# CellCircuit.net
KiCad netlist of a schematic drawn in Altium Designer
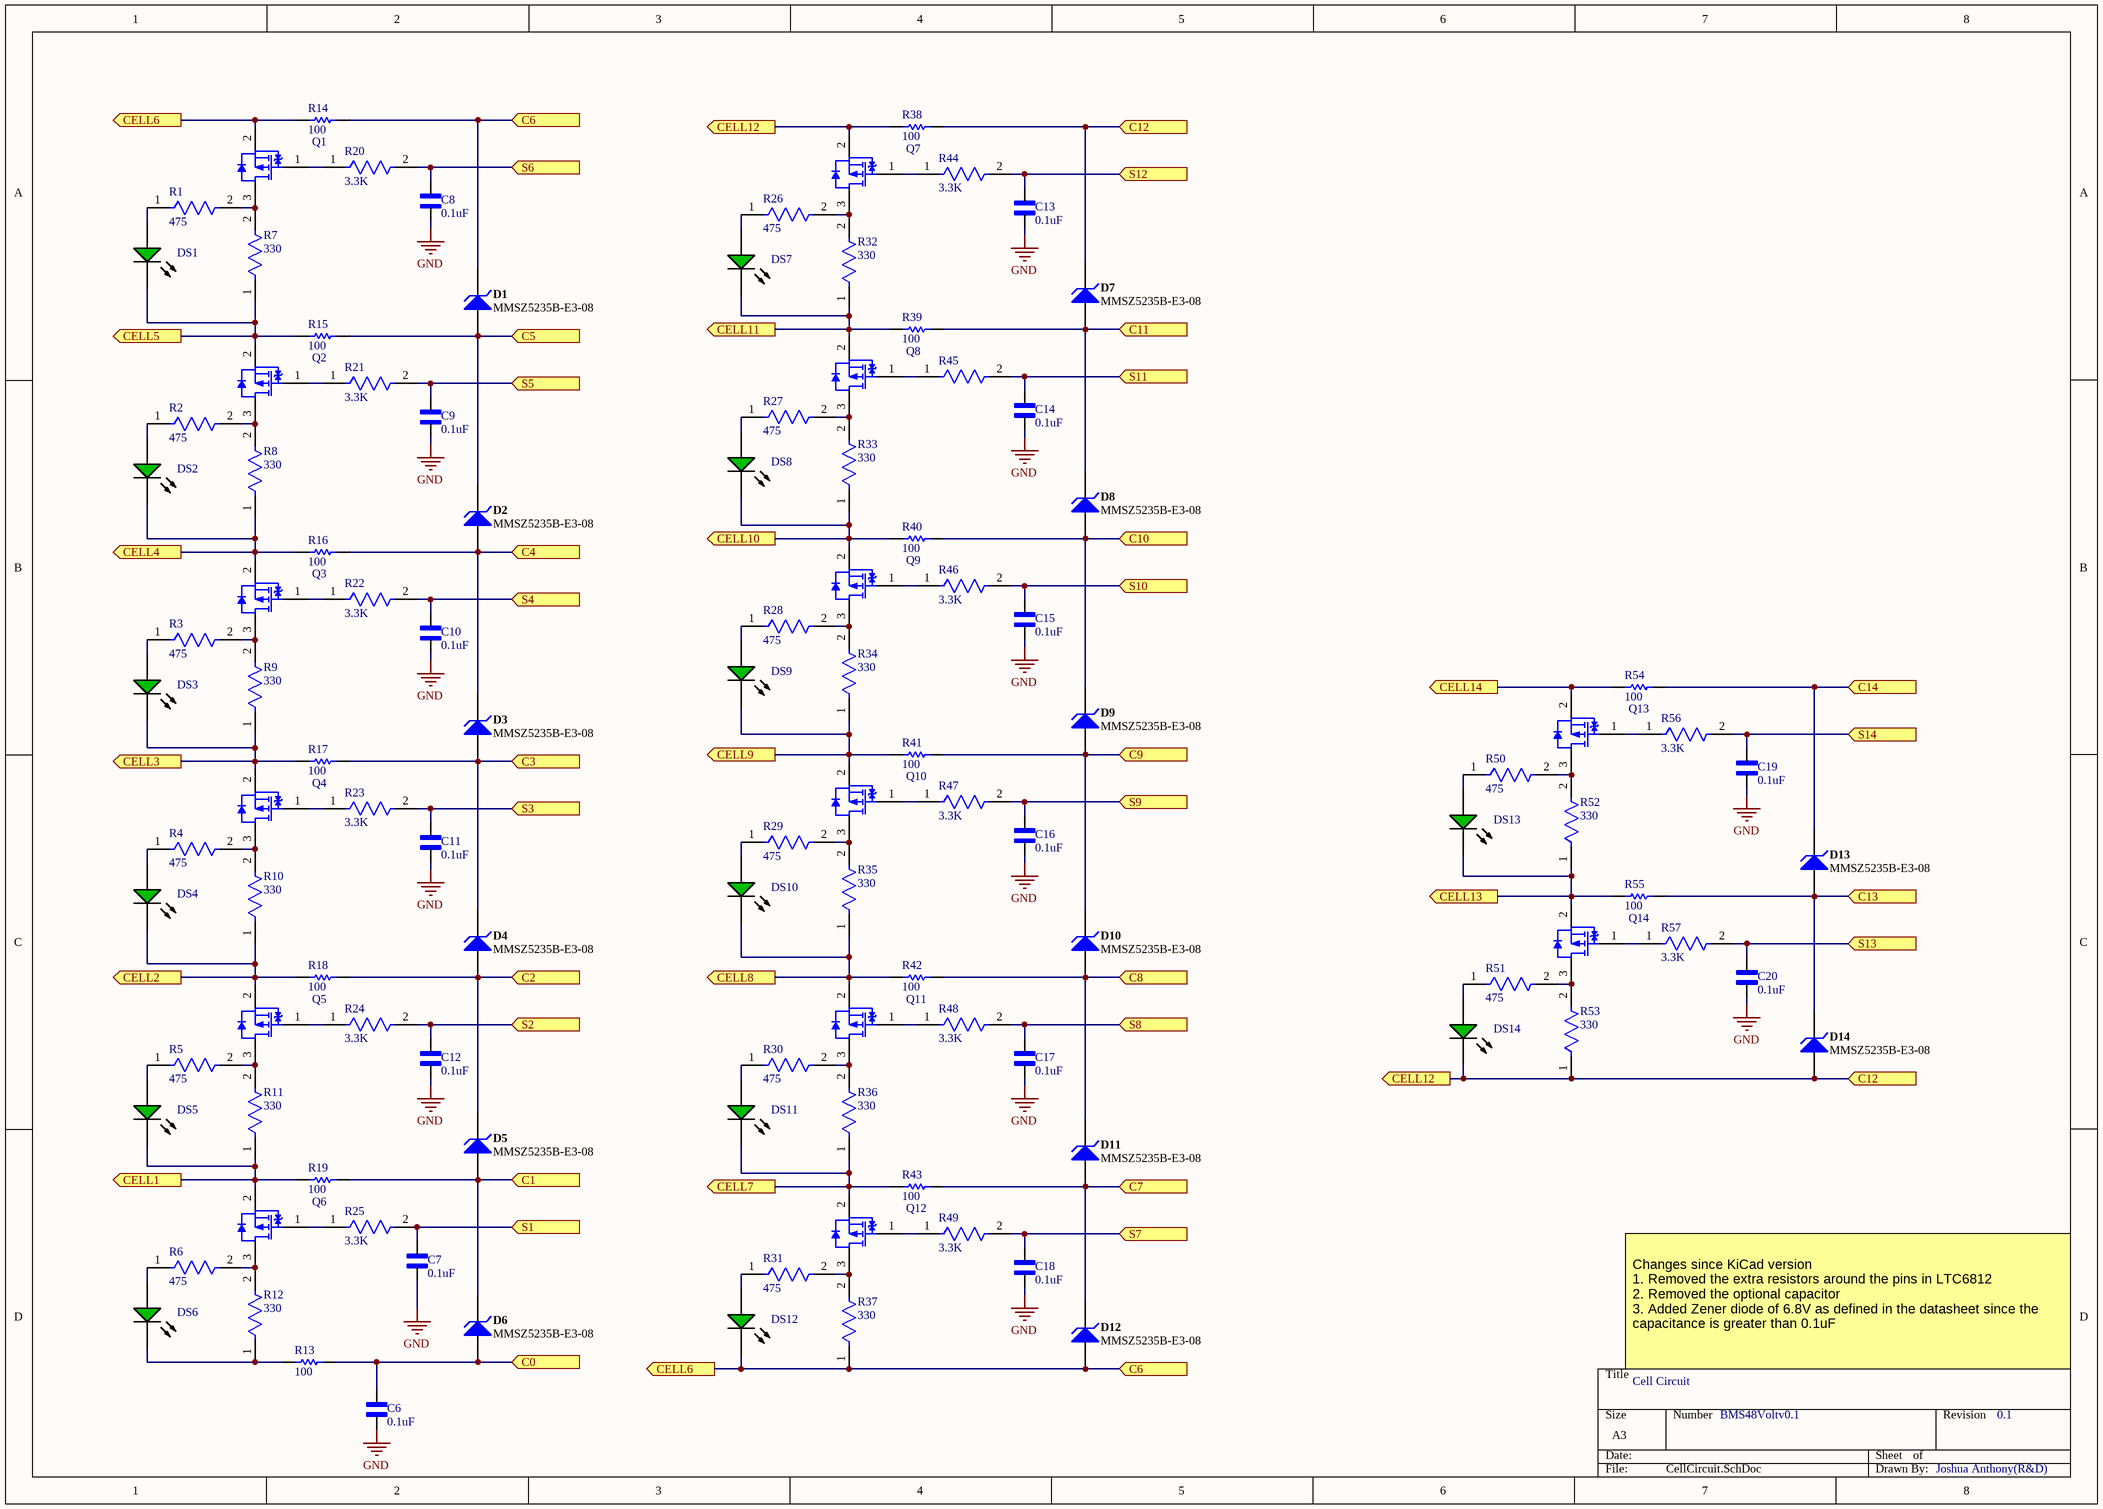
[diagram p0: CellCircuit.SchDoc]

(export (version "E")
  (design (tool "Eeschema 10.0.6"))
  (components
    (comp (ref "C6")
      (value "0.1uF")
      (footprint "CAPC1005X55N")
      (description "CAP CER 0.1UF 16V 10% X7R 0402")
      (fields (field (name "MF") "{'manufacturer': u'Murata'}") (field (name "MP") "GRM155R71C104KA88D"))
      (libsource (lib "SnapEDA_Library") (part "GRM155R71C104KA88D"))
    )
    (comp (ref "C7")
      (value "0.1uF")
      (footprint "CAPC1005X55N")
      (description "CAP CER 0.1UF 16V 10% X7R 0402")
      (fields (field (name "MF") "{'manufacturer': u'Murata'}") (field (name "MP") "GRM155R71C104KA88D"))
      (libsource (lib "SnapEDA_Library") (part "GRM155R71C104KA88D"))
    )
    (comp (ref "C8")
      (value "0.1uF")
      (footprint "CAPC1005X55N")
      (description "CAP CER 0.1UF 16V 10% X7R 0402")
      (fields (field (name "MF") "{'manufacturer': u'Murata'}") (field (name "MP") "GRM155R71C104KA88D"))
      (libsource (lib "SnapEDA_Library") (part "GRM155R71C104KA88D"))
    )
    (comp (ref "C9")
      (value "0.1uF")
      (footprint "CAPC1005X55N")
      (description "CAP CER 0.1UF 16V 10% X7R 0402")
      (fields (field (name "MF") "{'manufacturer': u'Murata'}") (field (name "MP") "GRM155R71C104KA88D"))
      (libsource (lib "SnapEDA_Library") (part "GRM155R71C104KA88D"))
    )
    (comp (ref "C10")
      (value "0.1uF")
      (footprint "CAPC1005X55N")
      (description "CAP CER 0.1UF 16V 10% X7R 0402")
      (fields (field (name "MF") "{'manufacturer': u'Murata'}") (field (name "MP") "GRM155R71C104KA88D"))
      (libsource (lib "SnapEDA_Library") (part "GRM155R71C104KA88D"))
    )
    (comp (ref "C11")
      (value "0.1uF")
      (footprint "CAPC1005X55N")
      (description "CAP CER 0.1UF 16V 10% X7R 0402")
      (fields (field (name "MF") "{'manufacturer': u'Murata'}") (field (name "MP") "GRM155R71C104KA88D"))
      (libsource (lib "SnapEDA_Library") (part "GRM155R71C104KA88D"))
    )
    (comp (ref "C12")
      (value "0.1uF")
      (footprint "CAPC1005X55N")
      (description "CAP CER 0.1UF 16V 10% X7R 0402")
      (fields (field (name "MF") "{'manufacturer': u'Murata'}") (field (name "MP") "GRM155R71C104KA88D"))
      (libsource (lib "SnapEDA_Library") (part "GRM155R71C104KA88D"))
    )
    (comp (ref "C13")
      (value "0.1uF")
      (footprint "CAPC1005X55N")
      (description "CAP CER 0.1UF 16V 10% X7R 0402")
      (fields (field (name "MF") "{'manufacturer': u'Murata'}") (field (name "MP") "GRM155R71C104KA88D"))
      (libsource (lib "SnapEDA_Library") (part "GRM155R71C104KA88D"))
    )
    (comp (ref "C14")
      (value "0.1uF")
      (footprint "CAPC1005X55N")
      (description "CAP CER 0.1UF 16V 10% X7R 0402")
      (fields (field (name "MF") "{'manufacturer': u'Murata'}") (field (name "MP") "GRM155R71C104KA88D"))
      (libsource (lib "SnapEDA_Library") (part "GRM155R71C104KA88D"))
    )
    (comp (ref "C15")
      (value "0.1uF")
      (footprint "CAPC1005X55N")
      (description "CAP CER 0.1UF 16V 10% X7R 0402")
      (fields (field (name "MF") "{'manufacturer': u'Murata'}") (field (name "MP") "GRM155R71C104KA88D"))
      (libsource (lib "SnapEDA_Library") (part "GRM155R71C104KA88D"))
    )
    (comp (ref "C16")
      (value "0.1uF")
      (footprint "CAPC1005X55N")
      (description "CAP CER 0.1UF 16V 10% X7R 0402")
      (fields (field (name "MF") "{'manufacturer': u'Murata'}") (field (name "MP") "GRM155R71C104KA88D"))
      (libsource (lib "SnapEDA_Library") (part "GRM155R71C104KA88D"))
    )
    (comp (ref "C17")
      (value "0.1uF")
      (footprint "CAPC1005X55N")
      (description "CAP CER 0.1UF 16V 10% X7R 0402")
      (fields (field (name "MF") "{'manufacturer': u'Murata'}") (field (name "MP") "GRM155R71C104KA88D"))
      (libsource (lib "SnapEDA_Library") (part "GRM155R71C104KA88D"))
    )
    (comp (ref "C18")
      (value "0.1uF")
      (footprint "CAPC1005X55N")
      (description "CAP CER 0.1UF 16V 10% X7R 0402")
      (fields (field (name "MF") "{'manufacturer': u'Murata'}") (field (name "MP") "GRM155R71C104KA88D"))
      (libsource (lib "SnapEDA_Library") (part "GRM155R71C104KA88D"))
    )
    (comp (ref "C19")
      (value "0.1uF")
      (footprint "CAPC1005X55N")
      (description "CAP CER 0.1UF 16V 10% X7R 0402")
      (fields (field (name "MF") "{'manufacturer': u'Murata'}") (field (name "MP") "GRM155R71C104KA88D"))
      (libsource (lib "SnapEDA_Library") (part "GRM155R71C104KA88D"))
    )
    (comp (ref "C20")
      (value "0.1uF")
      (footprint "CAPC1005X55N")
      (description "CAP CER 0.1UF 16V 10% X7R 0402")
      (fields (field (name "MF") "{'manufacturer': u'Murata'}") (field (name "MP") "GRM155R71C104KA88D"))
      (libsource (lib "SnapEDA_Library") (part "GRM155R71C104KA88D"))
    )
    (comp (ref "D1")
      (value "MMSZ5235B-E3-08")
      (footprint "VISH-SOD-123-2_V")
      (description "Small Signal Zener Diode, 6.8 V +/- 5%, -55 to 155 degC, 2-Pin SOD-123, RoHS, Tape and Reel")
      (fields (field (name "MANUFACTURER") "Vishay Semiconductor") (field (name "TOLERANCE") "+/- 5%"))
      (libsource (lib "Altium Content Vault") (part "VISH-DZEN_A1K2-2"))
    )
    (comp (ref "D2")
      (value "MMSZ5235B-E3-08")
      (footprint "VISH-SOD-123-2_V")
      (description "Small Signal Zener Diode, 6.8 V +/- 5%, -55 to 155 degC, 2-Pin SOD-123, RoHS, Tape and Reel")
      (fields (field (name "MANUFACTURER") "Vishay Semiconductor") (field (name "TOLERANCE") "+/- 5%"))
      (libsource (lib "Altium Content Vault") (part "VISH-DZEN_A1K2-2"))
    )
    (comp (ref "D3")
      (value "MMSZ5235B-E3-08")
      (footprint "VISH-SOD-123-2_V")
      (description "Small Signal Zener Diode, 6.8 V +/- 5%, -55 to 155 degC, 2-Pin SOD-123, RoHS, Tape and Reel")
      (fields (field (name "MANUFACTURER") "Vishay Semiconductor") (field (name "TOLERANCE") "+/- 5%"))
      (libsource (lib "Altium Content Vault") (part "VISH-DZEN_A1K2-2"))
    )
    (comp (ref "D4")
      (value "MMSZ5235B-E3-08")
      (footprint "VISH-SOD-123-2_V")
      (description "Small Signal Zener Diode, 6.8 V +/- 5%, -55 to 155 degC, 2-Pin SOD-123, RoHS, Tape and Reel")
      (fields (field (name "MANUFACTURER") "Vishay Semiconductor") (field (name "TOLERANCE") "+/- 5%"))
      (libsource (lib "Altium Content Vault") (part "VISH-DZEN_A1K2-2"))
    )
    (comp (ref "D5")
      (value "MMSZ5235B-E3-08")
      (footprint "VISH-SOD-123-2_V")
      (description "Small Signal Zener Diode, 6.8 V +/- 5%, -55 to 155 degC, 2-Pin SOD-123, RoHS, Tape and Reel")
      (fields (field (name "MANUFACTURER") "Vishay Semiconductor") (field (name "TOLERANCE") "+/- 5%"))
      (libsource (lib "Altium Content Vault") (part "VISH-DZEN_A1K2-2"))
    )
    (comp (ref "D6")
      (value "MMSZ5235B-E3-08")
      (footprint "VISH-SOD-123-2_V")
      (description "Small Signal Zener Diode, 6.8 V +/- 5%, -55 to 155 degC, 2-Pin SOD-123, RoHS, Tape and Reel")
      (fields (field (name "MANUFACTURER") "Vishay Semiconductor") (field (name "TOLERANCE") "+/- 5%"))
      (libsource (lib "Altium Content Vault") (part "VISH-DZEN_A1K2-2"))
    )
    (comp (ref "D7")
      (value "MMSZ5235B-E3-08")
      (footprint "VISH-SOD-123-2_V")
      (description "Small Signal Zener Diode, 6.8 V +/- 5%, -55 to 155 degC, 2-Pin SOD-123, RoHS, Tape and Reel")
      (fields (field (name "MANUFACTURER") "Vishay Semiconductor") (field (name "TOLERANCE") "+/- 5%"))
      (libsource (lib "Altium Content Vault") (part "VISH-DZEN_A1K2-2"))
    )
    (comp (ref "D8")
      (value "MMSZ5235B-E3-08")
      (footprint "VISH-SOD-123-2_V")
      (description "Small Signal Zener Diode, 6.8 V +/- 5%, -55 to 155 degC, 2-Pin SOD-123, RoHS, Tape and Reel")
      (fields (field (name "MANUFACTURER") "Vishay Semiconductor") (field (name "TOLERANCE") "+/- 5%"))
      (libsource (lib "Altium Content Vault") (part "VISH-DZEN_A1K2-2"))
    )
    (comp (ref "D9")
      (value "MMSZ5235B-E3-08")
      (footprint "VISH-SOD-123-2_V")
      (description "Small Signal Zener Diode, 6.8 V +/- 5%, -55 to 155 degC, 2-Pin SOD-123, RoHS, Tape and Reel")
      (fields (field (name "MANUFACTURER") "Vishay Semiconductor") (field (name "TOLERANCE") "+/- 5%"))
      (libsource (lib "Altium Content Vault") (part "VISH-DZEN_A1K2-2"))
    )
    (comp (ref "D10")
      (value "MMSZ5235B-E3-08")
      (footprint "VISH-SOD-123-2_V")
      (description "Small Signal Zener Diode, 6.8 V +/- 5%, -55 to 155 degC, 2-Pin SOD-123, RoHS, Tape and Reel")
      (fields (field (name "MANUFACTURER") "Vishay Semiconductor") (field (name "TOLERANCE") "+/- 5%"))
      (libsource (lib "Altium Content Vault") (part "VISH-DZEN_A1K2-2"))
    )
    (comp (ref "D11")
      (value "MMSZ5235B-E3-08")
      (footprint "VISH-SOD-123-2_V")
      (description "Small Signal Zener Diode, 6.8 V +/- 5%, -55 to 155 degC, 2-Pin SOD-123, RoHS, Tape and Reel")
      (fields (field (name "MANUFACTURER") "Vishay Semiconductor") (field (name "TOLERANCE") "+/- 5%"))
      (libsource (lib "Altium Content Vault") (part "VISH-DZEN_A1K2-2"))
    )
    (comp (ref "D12")
      (value "MMSZ5235B-E3-08")
      (footprint "VISH-SOD-123-2_V")
      (description "Small Signal Zener Diode, 6.8 V +/- 5%, -55 to 155 degC, 2-Pin SOD-123, RoHS, Tape and Reel")
      (fields (field (name "MANUFACTURER") "Vishay Semiconductor") (field (name "TOLERANCE") "+/- 5%"))
      (libsource (lib "Altium Content Vault") (part "VISH-DZEN_A1K2-2"))
    )
    (comp (ref "D13")
      (value "MMSZ5235B-E3-08")
      (footprint "VISH-SOD-123-2_V")
      (description "Small Signal Zener Diode, 6.8 V +/- 5%, -55 to 155 degC, 2-Pin SOD-123, RoHS, Tape and Reel")
      (fields (field (name "MANUFACTURER") "Vishay Semiconductor") (field (name "TOLERANCE") "+/- 5%"))
      (libsource (lib "Altium Content Vault") (part "VISH-DZEN_A1K2-2"))
    )
    (comp (ref "D14")
      (value "MMSZ5235B-E3-08")
      (footprint "VISH-SOD-123-2_V")
      (description "Small Signal Zener Diode, 6.8 V +/- 5%, -55 to 155 degC, 2-Pin SOD-123, RoHS, Tape and Reel")
      (fields (field (name "MANUFACTURER") "Vishay Semiconductor") (field (name "TOLERANCE") "+/- 5%"))
      (libsource (lib "Altium Content Vault") (part "VISH-DZEN_A1K2-2"))
    )
    (comp (ref "DS1")
      (value "HSMG-C170")
      (footprint "AVAG-HSMX-C170_V")
      (description "Chip LED, Green, 2.2 V, -40 to 85 degC, 2-Pin SMD, Pb-Free, Tape and Reel")
      (fields (field (name "MANUFACTURER") "Avago"))
      (libsource (lib "Altium Content Vault") (part "LED_GREEN_A1K2-2"))
    )
    (comp (ref "DS2")
      (value "HSMG-C170")
      (footprint "AVAG-HSMX-C170_V")
      (description "Chip LED, Green, 2.2 V, -40 to 85 degC, 2-Pin SMD, Pb-Free, Tape and Reel")
      (fields (field (name "MANUFACTURER") "Avago"))
      (libsource (lib "Altium Content Vault") (part "LED_GREEN_A1K2-2"))
    )
    (comp (ref "DS3")
      (value "HSMG-C170")
      (footprint "AVAG-HSMX-C170_V")
      (description "Chip LED, Green, 2.2 V, -40 to 85 degC, 2-Pin SMD, Pb-Free, Tape and Reel")
      (fields (field (name "MANUFACTURER") "Avago"))
      (libsource (lib "Altium Content Vault") (part "LED_GREEN_A1K2-2"))
    )
    (comp (ref "DS4")
      (value "HSMG-C170")
      (footprint "AVAG-HSMX-C170_V")
      (description "Chip LED, Green, 2.2 V, -40 to 85 degC, 2-Pin SMD, Pb-Free, Tape and Reel")
      (fields (field (name "MANUFACTURER") "Avago"))
      (libsource (lib "Altium Content Vault") (part "LED_GREEN_A1K2-2"))
    )
    (comp (ref "DS5")
      (value "HSMG-C170")
      (footprint "AVAG-HSMX-C170_V")
      (description "Chip LED, Green, 2.2 V, -40 to 85 degC, 2-Pin SMD, Pb-Free, Tape and Reel")
      (fields (field (name "MANUFACTURER") "Avago"))
      (libsource (lib "Altium Content Vault") (part "LED_GREEN_A1K2-2"))
    )
    (comp (ref "DS6")
      (value "HSMG-C170")
      (footprint "AVAG-HSMX-C170_V")
      (description "Chip LED, Green, 2.2 V, -40 to 85 degC, 2-Pin SMD, Pb-Free, Tape and Reel")
      (fields (field (name "MANUFACTURER") "Avago"))
      (libsource (lib "Altium Content Vault") (part "LED_GREEN_A1K2-2"))
    )
    (comp (ref "DS7")
      (value "HSMG-C170")
      (footprint "AVAG-HSMX-C170_V")
      (description "Chip LED, Green, 2.2 V, -40 to 85 degC, 2-Pin SMD, Pb-Free, Tape and Reel")
      (fields (field (name "MANUFACTURER") "Avago"))
      (libsource (lib "Altium Content Vault") (part "LED_GREEN_A1K2-2"))
    )
    (comp (ref "DS8")
      (value "HSMG-C170")
      (footprint "AVAG-HSMX-C170_V")
      (description "Chip LED, Green, 2.2 V, -40 to 85 degC, 2-Pin SMD, Pb-Free, Tape and Reel")
      (fields (field (name "MANUFACTURER") "Avago"))
      (libsource (lib "Altium Content Vault") (part "LED_GREEN_A1K2-2"))
    )
    (comp (ref "DS9")
      (value "HSMG-C170")
      (footprint "AVAG-HSMX-C170_V")
      (description "Chip LED, Green, 2.2 V, -40 to 85 degC, 2-Pin SMD, Pb-Free, Tape and Reel")
      (fields (field (name "MANUFACTURER") "Avago"))
      (libsource (lib "Altium Content Vault") (part "LED_GREEN_A1K2-2"))
    )
    (comp (ref "DS10")
      (value "HSMG-C170")
      (footprint "AVAG-HSMX-C170_V")
      (description "Chip LED, Green, 2.2 V, -40 to 85 degC, 2-Pin SMD, Pb-Free, Tape and Reel")
      (fields (field (name "MANUFACTURER") "Avago"))
      (libsource (lib "Altium Content Vault") (part "LED_GREEN_A1K2-2"))
    )
    (comp (ref "DS11")
      (value "HSMG-C170")
      (footprint "AVAG-HSMX-C170_V")
      (description "Chip LED, Green, 2.2 V, -40 to 85 degC, 2-Pin SMD, Pb-Free, Tape and Reel")
      (fields (field (name "MANUFACTURER") "Avago"))
      (libsource (lib "Altium Content Vault") (part "LED_GREEN_A1K2-2"))
    )
    (comp (ref "DS12")
      (value "HSMG-C170")
      (footprint "AVAG-HSMX-C170_V")
      (description "Chip LED, Green, 2.2 V, -40 to 85 degC, 2-Pin SMD, Pb-Free, Tape and Reel")
      (fields (field (name "MANUFACTURER") "Avago"))
      (libsource (lib "Altium Content Vault") (part "LED_GREEN_A1K2-2"))
    )
    (comp (ref "DS13")
      (value "HSMG-C170")
      (footprint "AVAG-HSMX-C170_V")
      (description "Chip LED, Green, 2.2 V, -40 to 85 degC, 2-Pin SMD, Pb-Free, Tape and Reel")
      (fields (field (name "MANUFACTURER") "Avago"))
      (libsource (lib "Altium Content Vault") (part "LED_GREEN_A1K2-2"))
    )
    (comp (ref "DS14")
      (value "HSMG-C170")
      (footprint "AVAG-HSMX-C170_V")
      (description "Chip LED, Green, 2.2 V, -40 to 85 degC, 2-Pin SMD, Pb-Free, Tape and Reel")
      (fields (field (name "MANUFACTURER") "Avago"))
      (libsource (lib "Altium Content Vault") (part "LED_GREEN_A1K2-2"))
    )
    (comp (ref "Q1")
      (value "BSS308PE")
      (footprint "INF-PG-SOT23_L")
      (fields (field (name "MANUFACTURER") "Infineon"))
      (libsource (lib "Altium Content Vault") (part "INF-BSS3XXPE-PG-SOT23-3"))
    )
    (comp (ref "Q2")
      (value "BSS308PE")
      (footprint "INF-PG-SOT23_L")
      (fields (field (name "MANUFACTURER") "Infineon"))
      (libsource (lib "Altium Content Vault") (part "INF-BSS3XXPE-PG-SOT23-3"))
    )
    (comp (ref "Q3")
      (value "BSS308PE")
      (footprint "INF-PG-SOT23_L")
      (fields (field (name "MANUFACTURER") "Infineon"))
      (libsource (lib "Altium Content Vault") (part "INF-BSS3XXPE-PG-SOT23-3"))
    )
    (comp (ref "Q4")
      (value "BSS308PE")
      (footprint "INF-PG-SOT23_L")
      (fields (field (name "MANUFACTURER") "Infineon"))
      (libsource (lib "Altium Content Vault") (part "INF-BSS3XXPE-PG-SOT23-3"))
    )
    (comp (ref "Q5")
      (value "BSS308PE")
      (footprint "INF-PG-SOT23_L")
      (fields (field (name "MANUFACTURER") "Infineon"))
      (libsource (lib "Altium Content Vault") (part "INF-BSS3XXPE-PG-SOT23-3"))
    )
    (comp (ref "Q6")
      (value "BSS308PE")
      (footprint "INF-PG-SOT23_L")
      (fields (field (name "MANUFACTURER") "Infineon"))
      (libsource (lib "Altium Content Vault") (part "INF-BSS3XXPE-PG-SOT23-3"))
    )
    (comp (ref "Q7")
      (value "BSS308PE")
      (footprint "INF-PG-SOT23_L")
      (fields (field (name "MANUFACTURER") "Infineon"))
      (libsource (lib "Altium Content Vault") (part "INF-BSS3XXPE-PG-SOT23-3"))
    )
    (comp (ref "Q8")
      (value "BSS308PE")
      (footprint "INF-PG-SOT23_L")
      (fields (field (name "MANUFACTURER") "Infineon"))
      (libsource (lib "Altium Content Vault") (part "INF-BSS3XXPE-PG-SOT23-3"))
    )
    (comp (ref "Q9")
      (value "BSS308PE")
      (footprint "INF-PG-SOT23_L")
      (fields (field (name "MANUFACTURER") "Infineon"))
      (libsource (lib "Altium Content Vault") (part "INF-BSS3XXPE-PG-SOT23-3"))
    )
    (comp (ref "Q10")
      (value "BSS308PE")
      (footprint "INF-PG-SOT23_L")
      (fields (field (name "MANUFACTURER") "Infineon"))
      (libsource (lib "Altium Content Vault") (part "INF-BSS3XXPE-PG-SOT23-3"))
    )
    (comp (ref "Q11")
      (value "BSS308PE")
      (footprint "INF-PG-SOT23_L")
      (fields (field (name "MANUFACTURER") "Infineon"))
      (libsource (lib "Altium Content Vault") (part "INF-BSS3XXPE-PG-SOT23-3"))
    )
    (comp (ref "Q12")
      (value "BSS308PE")
      (footprint "INF-PG-SOT23_L")
      (fields (field (name "MANUFACTURER") "Infineon"))
      (libsource (lib "Altium Content Vault") (part "INF-BSS3XXPE-PG-SOT23-3"))
    )
    (comp (ref "Q13")
      (value "BSS308PE")
      (footprint "INF-PG-SOT23_L")
      (fields (field (name "MANUFACTURER") "Infineon"))
      (libsource (lib "Altium Content Vault") (part "INF-BSS3XXPE-PG-SOT23-3"))
    )
    (comp (ref "Q14")
      (value "BSS308PE")
      (footprint "INF-PG-SOT23_L")
      (fields (field (name "MANUFACTURER") "Infineon"))
      (libsource (lib "Altium Content Vault") (part "INF-BSS3XXPE-PG-SOT23-3"))
    )
    (comp (ref "R1")
      (value "475")
      (footprint "FP-CRCW0402-e3-IPC_C")
      (description "RES Thick Film, 475Ω, 1%, 0.063W, 100ppm/°C, 0402")
      (fields (field (name "TOLERANCE") "1%"))
      (libsource (lib "Altium Content Vault") (part "1029c3af85768c4190bb7ad29bc67b5"))
    )
    (comp (ref "R2")
      (value "475")
      (footprint "FP-CRCW0402-e3-IPC_C")
      (description "RES Thick Film, 475Ω, 1%, 0.063W, 100ppm/°C, 0402")
      (fields (field (name "TOLERANCE") "1%"))
      (libsource (lib "Altium Content Vault") (part "1029c3af85768c4190bb7ad29bc67b5"))
    )
    (comp (ref "R3")
      (value "475")
      (footprint "FP-CRCW0402-e3-IPC_C")
      (description "RES Thick Film, 475Ω, 1%, 0.063W, 100ppm/°C, 0402")
      (fields (field (name "TOLERANCE") "1%"))
      (libsource (lib "Altium Content Vault") (part "1029c3af85768c4190bb7ad29bc67b5"))
    )
    (comp (ref "R4")
      (value "475")
      (footprint "FP-CRCW0402-e3-IPC_C")
      (description "RES Thick Film, 475Ω, 1%, 0.063W, 100ppm/°C, 0402")
      (fields (field (name "TOLERANCE") "1%"))
      (libsource (lib "Altium Content Vault") (part "1029c3af85768c4190bb7ad29bc67b5"))
    )
    (comp (ref "R5")
      (value "475")
      (footprint "FP-CRCW0402-e3-IPC_C")
      (description "RES Thick Film, 475Ω, 1%, 0.063W, 100ppm/°C, 0402")
      (fields (field (name "TOLERANCE") "1%"))
      (libsource (lib "Altium Content Vault") (part "1029c3af85768c4190bb7ad29bc67b5"))
    )
    (comp (ref "R6")
      (value "475")
      (footprint "FP-CRCW0402-e3-IPC_C")
      (description "RES Thick Film, 475Ω, 1%, 0.063W, 100ppm/°C, 0402")
      (fields (field (name "TOLERANCE") "1%"))
      (libsource (lib "Altium Content Vault") (part "1029c3af85768c4190bb7ad29bc67b5"))
    )
    (comp (ref "R7")
      (value "330")
      (footprint "FP-CRCW0603-e3-MFG")
      (description "RES Thick Film, 330Ω, 1%, 0.1W, 100ppm/°C, 0603")
      (fields (field (name "TOLERANCE") "1%"))
      (libsource (lib "Altium Content Vault") (part "1029c3af85768c4190bb7ad29bc67b5"))
    )
    (comp (ref "R8")
      (value "330")
      (footprint "FP-CRCW0603-e3-MFG")
      (description "RES Thick Film, 330Ω, 1%, 0.1W, 100ppm/°C, 0603")
      (fields (field (name "TOLERANCE") "1%"))
      (libsource (lib "Altium Content Vault") (part "1029c3af85768c4190bb7ad29bc67b5"))
    )
    (comp (ref "R9")
      (value "330")
      (footprint "FP-CRCW0603-e3-MFG")
      (description "RES Thick Film, 330Ω, 1%, 0.1W, 100ppm/°C, 0603")
      (fields (field (name "TOLERANCE") "1%"))
      (libsource (lib "Altium Content Vault") (part "1029c3af85768c4190bb7ad29bc67b5"))
    )
    (comp (ref "R10")
      (value "330")
      (footprint "FP-CRCW0603-e3-MFG")
      (description "RES Thick Film, 330Ω, 1%, 0.1W, 100ppm/°C, 0603")
      (fields (field (name "TOLERANCE") "1%"))
      (libsource (lib "Altium Content Vault") (part "1029c3af85768c4190bb7ad29bc67b5"))
    )
    (comp (ref "R11")
      (value "330")
      (footprint "FP-CRCW0603-e3-MFG")
      (description "RES Thick Film, 330Ω, 1%, 0.1W, 100ppm/°C, 0603")
      (fields (field (name "TOLERANCE") "1%"))
      (libsource (lib "Altium Content Vault") (part "1029c3af85768c4190bb7ad29bc67b5"))
    )
    (comp (ref "R12")
      (value "330")
      (footprint "FP-CRCW0603-e3-MFG")
      (description "RES Thick Film, 330Ω, 1%, 0.1W, 100ppm/°C, 0603")
      (fields (field (name "TOLERANCE") "1%"))
      (libsource (lib "Altium Content Vault") (part "1029c3af85768c4190bb7ad29bc67b5"))
    )
    (comp (ref "R13")
      (value "100")
      (footprint "RESC1005X40X25LL05T05")
      (description "Chip Resistor, 100 Ohm, +/- 1%, 100 mW, -55 to 155 degC, 0402 (1005 Metric), RoHS, Tape and Reel")
      (fields (field (name "MANUFACTURER") "Basic Passives") (field (name "TOLERANCE") "1%"))
      (libsource (lib "Altium Content Vault") (part "RES-2"))
    )
    (comp (ref "R14")
      (value "100")
      (footprint "RESC1005X40X25LL05T05")
      (description "Chip Resistor, 100 Ohm, +/- 1%, 100 mW, -55 to 155 degC, 0402 (1005 Metric), RoHS, Tape and Reel")
      (fields (field (name "MANUFACTURER") "Basic Passives") (field (name "TOLERANCE") "1%"))
      (libsource (lib "Altium Content Vault") (part "RES-2"))
    )
    (comp (ref "R15")
      (value "100")
      (footprint "RESC1005X40X25LL05T05")
      (description "Chip Resistor, 100 Ohm, +/- 1%, 100 mW, -55 to 155 degC, 0402 (1005 Metric), RoHS, Tape and Reel")
      (fields (field (name "MANUFACTURER") "Basic Passives") (field (name "TOLERANCE") "1%"))
      (libsource (lib "Altium Content Vault") (part "RES-2"))
    )
    (comp (ref "R16")
      (value "100")
      (footprint "RESC1005X40X25LL05T05")
      (description "Chip Resistor, 100 Ohm, +/- 1%, 100 mW, -55 to 155 degC, 0402 (1005 Metric), RoHS, Tape and Reel")
      (fields (field (name "MANUFACTURER") "Basic Passives") (field (name "TOLERANCE") "1%"))
      (libsource (lib "Altium Content Vault") (part "RES-2"))
    )
    (comp (ref "R17")
      (value "100")
      (footprint "RESC1005X40X25LL05T05")
      (description "Chip Resistor, 100 Ohm, +/- 1%, 100 mW, -55 to 155 degC, 0402 (1005 Metric), RoHS, Tape and Reel")
      (fields (field (name "MANUFACTURER") "Basic Passives") (field (name "TOLERANCE") "1%"))
      (libsource (lib "Altium Content Vault") (part "RES-2"))
    )
    (comp (ref "R18")
      (value "100")
      (footprint "RESC1005X40X25LL05T05")
      (description "Chip Resistor, 100 Ohm, +/- 1%, 100 mW, -55 to 155 degC, 0402 (1005 Metric), RoHS, Tape and Reel")
      (fields (field (name "MANUFACTURER") "Basic Passives") (field (name "TOLERANCE") "1%"))
      (libsource (lib "Altium Content Vault") (part "RES-2"))
    )
    (comp (ref "R19")
      (value "100")
      (footprint "RESC1005X40X25LL05T05")
      (description "Chip Resistor, 100 Ohm, +/- 1%, 100 mW, -55 to 155 degC, 0402 (1005 Metric), RoHS, Tape and Reel")
      (fields (field (name "MANUFACTURER") "Basic Passives") (field (name "TOLERANCE") "1%"))
      (libsource (lib "Altium Content Vault") (part "RES-2"))
    )
    (comp (ref "R20")
      (value "3.3K")
      (footprint "FP-RMCF2512-IPC_C")
      (description "3.3kΩ ±5% 1W 2512 Thick Film Chip Resistor AEC-Q200 compliant")
      (fields (field (name "TOLERANCE") "5%"))
      (libsource (lib "Altium Content Vault") (part "1029c3af85768c4190bb7ad29bc67b5"))
    )
    (comp (ref "R21")
      (value "3.3K")
      (footprint "FP-RMCF2512-IPC_C")
      (description "3.3kΩ ±5% 1W 2512 Thick Film Chip Resistor AEC-Q200 compliant")
      (fields (field (name "TOLERANCE") "5%"))
      (libsource (lib "Altium Content Vault") (part "1029c3af85768c4190bb7ad29bc67b5"))
    )
    (comp (ref "R22")
      (value "3.3K")
      (footprint "FP-RMCF2512-IPC_C")
      (description "3.3kΩ ±5% 1W 2512 Thick Film Chip Resistor AEC-Q200 compliant")
      (fields (field (name "TOLERANCE") "5%"))
      (libsource (lib "Altium Content Vault") (part "1029c3af85768c4190bb7ad29bc67b5"))
    )
    (comp (ref "R23")
      (value "3.3K")
      (footprint "FP-RMCF2512-IPC_C")
      (description "3.3kΩ ±5% 1W 2512 Thick Film Chip Resistor AEC-Q200 compliant")
      (fields (field (name "TOLERANCE") "5%"))
      (libsource (lib "Altium Content Vault") (part "1029c3af85768c4190bb7ad29bc67b5"))
    )
    (comp (ref "R24")
      (value "3.3K")
      (footprint "FP-RMCF2512-IPC_C")
      (description "3.3kΩ ±5% 1W 2512 Thick Film Chip Resistor AEC-Q200 compliant")
      (fields (field (name "TOLERANCE") "5%"))
      (libsource (lib "Altium Content Vault") (part "1029c3af85768c4190bb7ad29bc67b5"))
    )
    (comp (ref "R25")
      (value "3.3K")
      (footprint "FP-RMCF2512-IPC_C")
      (description "3.3kΩ ±5% 1W 2512 Thick Film Chip Resistor AEC-Q200 compliant")
      (fields (field (name "TOLERANCE") "5%"))
      (libsource (lib "Altium Content Vault") (part "1029c3af85768c4190bb7ad29bc67b5"))
    )
    (comp (ref "R26")
      (value "475")
      (footprint "FP-CRCW0402-e3-IPC_C")
      (description "RES Thick Film, 475Ω, 1%, 0.063W, 100ppm/°C, 0402")
      (fields (field (name "TOLERANCE") "1%"))
      (libsource (lib "Altium Content Vault") (part "1029c3af85768c4190bb7ad29bc67b5"))
    )
    (comp (ref "R27")
      (value "475")
      (footprint "FP-CRCW0402-e3-IPC_C")
      (description "RES Thick Film, 475Ω, 1%, 0.063W, 100ppm/°C, 0402")
      (fields (field (name "TOLERANCE") "1%"))
      (libsource (lib "Altium Content Vault") (part "1029c3af85768c4190bb7ad29bc67b5"))
    )
    (comp (ref "R28")
      (value "475")
      (footprint "FP-CRCW0402-e3-IPC_C")
      (description "RES Thick Film, 475Ω, 1%, 0.063W, 100ppm/°C, 0402")
      (fields (field (name "TOLERANCE") "1%"))
      (libsource (lib "Altium Content Vault") (part "1029c3af85768c4190bb7ad29bc67b5"))
    )
    (comp (ref "R29")
      (value "475")
      (footprint "FP-CRCW0402-e3-IPC_C")
      (description "RES Thick Film, 475Ω, 1%, 0.063W, 100ppm/°C, 0402")
      (fields (field (name "TOLERANCE") "1%"))
      (libsource (lib "Altium Content Vault") (part "1029c3af85768c4190bb7ad29bc67b5"))
    )
    (comp (ref "R30")
      (value "475")
      (footprint "FP-CRCW0402-e3-IPC_C")
      (description "RES Thick Film, 475Ω, 1%, 0.063W, 100ppm/°C, 0402")
      (fields (field (name "TOLERANCE") "1%"))
      (libsource (lib "Altium Content Vault") (part "1029c3af85768c4190bb7ad29bc67b5"))
    )
    (comp (ref "R31")
      (value "475")
      (footprint "FP-CRCW0402-e3-IPC_C")
      (description "RES Thick Film, 475Ω, 1%, 0.063W, 100ppm/°C, 0402")
      (fields (field (name "TOLERANCE") "1%"))
      (libsource (lib "Altium Content Vault") (part "1029c3af85768c4190bb7ad29bc67b5"))
    )
    (comp (ref "R32")
      (value "330")
      (footprint "FP-CRCW0603-e3-MFG")
      (description "RES Thick Film, 330Ω, 1%, 0.1W, 100ppm/°C, 0603")
      (fields (field (name "TOLERANCE") "1%"))
      (libsource (lib "Altium Content Vault") (part "1029c3af85768c4190bb7ad29bc67b5"))
    )
    (comp (ref "R33")
      (value "330")
      (footprint "FP-CRCW0603-e3-MFG")
      (description "RES Thick Film, 330Ω, 1%, 0.1W, 100ppm/°C, 0603")
      (fields (field (name "TOLERANCE") "1%"))
      (libsource (lib "Altium Content Vault") (part "1029c3af85768c4190bb7ad29bc67b5"))
    )
    (comp (ref "R34")
      (value "330")
      (footprint "FP-CRCW0603-e3-MFG")
      (description "RES Thick Film, 330Ω, 1%, 0.1W, 100ppm/°C, 0603")
      (fields (field (name "TOLERANCE") "1%"))
      (libsource (lib "Altium Content Vault") (part "1029c3af85768c4190bb7ad29bc67b5"))
    )
    (comp (ref "R35")
      (value "330")
      (footprint "FP-CRCW0603-e3-MFG")
      (description "RES Thick Film, 330Ω, 1%, 0.1W, 100ppm/°C, 0603")
      (fields (field (name "TOLERANCE") "1%"))
      (libsource (lib "Altium Content Vault") (part "1029c3af85768c4190bb7ad29bc67b5"))
    )
    (comp (ref "R36")
      (value "330")
      (footprint "FP-CRCW0603-e3-MFG")
      (description "RES Thick Film, 330Ω, 1%, 0.1W, 100ppm/°C, 0603")
      (fields (field (name "TOLERANCE") "1%"))
      (libsource (lib "Altium Content Vault") (part "1029c3af85768c4190bb7ad29bc67b5"))
    )
    (comp (ref "R37")
      (value "330")
      (footprint "FP-CRCW0603-e3-MFG")
      (description "RES Thick Film, 330Ω, 1%, 0.1W, 100ppm/°C, 0603")
      (fields (field (name "TOLERANCE") "1%"))
      (libsource (lib "Altium Content Vault") (part "1029c3af85768c4190bb7ad29bc67b5"))
    )
    (comp (ref "R38")
      (value "100")
      (footprint "RESC1005X40X25LL05T05")
      (description "Chip Resistor, 100 Ohm, +/- 1%, 100 mW, -55 to 155 degC, 0402 (1005 Metric), RoHS, Tape and Reel")
      (fields (field (name "MANUFACTURER") "Basic Passives") (field (name "TOLERANCE") "1%"))
      (libsource (lib "Altium Content Vault") (part "RES-2"))
    )
    (comp (ref "R39")
      (value "100")
      (footprint "RESC1005X40X25LL05T05")
      (description "Chip Resistor, 100 Ohm, +/- 1%, 100 mW, -55 to 155 degC, 0402 (1005 Metric), RoHS, Tape and Reel")
      (fields (field (name "MANUFACTURER") "Basic Passives") (field (name "TOLERANCE") "1%"))
      (libsource (lib "Altium Content Vault") (part "RES-2"))
    )
    (comp (ref "R40")
      (value "100")
      (footprint "RESC1005X40X25LL05T05")
      (description "Chip Resistor, 100 Ohm, +/- 1%, 100 mW, -55 to 155 degC, 0402 (1005 Metric), RoHS, Tape and Reel")
      (fields (field (name "MANUFACTURER") "Basic Passives") (field (name "TOLERANCE") "1%"))
      (libsource (lib "Altium Content Vault") (part "RES-2"))
    )
    (comp (ref "R41")
      (value "100")
      (footprint "RESC1005X40X25LL05T05")
      (description "Chip Resistor, 100 Ohm, +/- 1%, 100 mW, -55 to 155 degC, 0402 (1005 Metric), RoHS, Tape and Reel")
      (fields (field (name "MANUFACTURER") "Basic Passives") (field (name "TOLERANCE") "1%"))
      (libsource (lib "Altium Content Vault") (part "RES-2"))
    )
    (comp (ref "R42")
      (value "100")
      (footprint "RESC1005X40X25LL05T05")
      (description "Chip Resistor, 100 Ohm, +/- 1%, 100 mW, -55 to 155 degC, 0402 (1005 Metric), RoHS, Tape and Reel")
      (fields (field (name "MANUFACTURER") "Basic Passives") (field (name "TOLERANCE") "1%"))
      (libsource (lib "Altium Content Vault") (part "RES-2"))
    )
    (comp (ref "R43")
      (value "100")
      (footprint "RESC1005X40X25LL05T05")
      (description "Chip Resistor, 100 Ohm, +/- 1%, 100 mW, -55 to 155 degC, 0402 (1005 Metric), RoHS, Tape and Reel")
      (fields (field (name "MANUFACTURER") "Basic Passives") (field (name "TOLERANCE") "1%"))
      (libsource (lib "Altium Content Vault") (part "RES-2"))
    )
    (comp (ref "R44")
      (value "3.3K")
      (footprint "FP-RMCF2512-IPC_C")
      (description "3.3kΩ ±5% 1W 2512 Thick Film Chip Resistor AEC-Q200 compliant")
      (fields (field (name "TOLERANCE") "5%"))
      (libsource (lib "Altium Content Vault") (part "1029c3af85768c4190bb7ad29bc67b5"))
    )
    (comp (ref "R45")
      (value "RMCF2512JT3K30")
      (footprint "FP-RMCF2512-IPC_C")
      (description "3.3kΩ ±5% 1W 2512 Thick Film Chip Resistor AEC-Q200 compliant")
      (fields (field (name "TOLERANCE") "5%"))
      (libsource (lib "Altium Content Vault") (part "1029c3af85768c4190bb7ad29bc67b5"))
    )
    (comp (ref "R46")
      (value "3.3K")
      (footprint "FP-RMCF2512-IPC_C")
      (description "3.3kΩ ±5% 1W 2512 Thick Film Chip Resistor AEC-Q200 compliant")
      (fields (field (name "TOLERANCE") "5%"))
      (libsource (lib "Altium Content Vault") (part "1029c3af85768c4190bb7ad29bc67b5"))
    )
    (comp (ref "R47")
      (value "3.3K")
      (footprint "FP-RMCF2512-IPC_C")
      (description "3.3kΩ ±5% 1W 2512 Thick Film Chip Resistor AEC-Q200 compliant")
      (fields (field (name "TOLERANCE") "5%"))
      (libsource (lib "Altium Content Vault") (part "1029c3af85768c4190bb7ad29bc67b5"))
    )
    (comp (ref "R48")
      (value "3.3K")
      (footprint "FP-RMCF2512-IPC_C")
      (description "3.3kΩ ±5% 1W 2512 Thick Film Chip Resistor AEC-Q200 compliant")
      (fields (field (name "TOLERANCE") "5%"))
      (libsource (lib "Altium Content Vault") (part "1029c3af85768c4190bb7ad29bc67b5"))
    )
    (comp (ref "R49")
      (value "3.3K")
      (footprint "FP-RMCF2512-IPC_C")
      (description "3.3kΩ ±5% 1W 2512 Thick Film Chip Resistor AEC-Q200 compliant")
      (fields (field (name "TOLERANCE") "5%"))
      (libsource (lib "Altium Content Vault") (part "1029c3af85768c4190bb7ad29bc67b5"))
    )
    (comp (ref "R50")
      (value "475")
      (footprint "FP-CRCW0402-e3-IPC_C")
      (description "RES Thick Film, 475Ω, 1%, 0.063W, 100ppm/°C, 0402")
      (fields (field (name "TOLERANCE") "1%"))
      (libsource (lib "Altium Content Vault") (part "1029c3af85768c4190bb7ad29bc67b5"))
    )
    (comp (ref "R51")
      (value "475")
      (footprint "FP-CRCW0402-e3-IPC_C")
      (description "RES Thick Film, 475Ω, 1%, 0.063W, 100ppm/°C, 0402")
      (fields (field (name "TOLERANCE") "1%"))
      (libsource (lib "Altium Content Vault") (part "1029c3af85768c4190bb7ad29bc67b5"))
    )
    (comp (ref "R52")
      (value "330")
      (footprint "FP-CRCW0603-e3-MFG")
      (description "RES Thick Film, 330Ω, 1%, 0.1W, 100ppm/°C, 0603")
      (fields (field (name "TOLERANCE") "1%"))
      (libsource (lib "Altium Content Vault") (part "1029c3af85768c4190bb7ad29bc67b5"))
    )
    (comp (ref "R53")
      (value "330")
      (footprint "FP-CRCW0603-e3-MFG")
      (description "RES Thick Film, 330Ω, 1%, 0.1W, 100ppm/°C, 0603")
      (fields (field (name "TOLERANCE") "1%"))
      (libsource (lib "Altium Content Vault") (part "1029c3af85768c4190bb7ad29bc67b5"))
    )
    (comp (ref "R54")
      (value "100")
      (footprint "RESC1005X40X25LL05T05")
      (description "Chip Resistor, 100 Ohm, +/- 1%, 100 mW, -55 to 155 degC, 0402 (1005 Metric), RoHS, Tape and Reel")
      (fields (field (name "MANUFACTURER") "Basic Passives") (field (name "TOLERANCE") "1%"))
      (libsource (lib "Altium Content Vault") (part "RES-2"))
    )
    (comp (ref "R55")
      (value "100")
      (footprint "RESC1005X40X25LL05T05")
      (description "Chip Resistor, 100 Ohm, +/- 1%, 100 mW, -55 to 155 degC, 0402 (1005 Metric), RoHS, Tape and Reel")
      (fields (field (name "MANUFACTURER") "Basic Passives") (field (name "TOLERANCE") "1%"))
      (libsource (lib "Altium Content Vault") (part "RES-2"))
    )
    (comp (ref "R56")
      (value "3.3K")
      (footprint "FP-RMCF2512-IPC_C")
      (description "3.3kΩ ±5% 1W 2512 Thick Film Chip Resistor AEC-Q200 compliant")
      (fields (field (name "TOLERANCE") "5%"))
      (libsource (lib "Altium Content Vault") (part "1029c3af85768c4190bb7ad29bc67b5"))
    )
    (comp (ref "R57")
      (value "3.3K")
      (footprint "FP-RMCF2512-IPC_C")
      (description "3.3kΩ ±5% 1W 2512 Thick Film Chip Resistor AEC-Q200 compliant")
      (fields (field (name "TOLERANCE") "5%"))
      (libsource (lib "Altium Content Vault") (part "1029c3af85768c4190bb7ad29bc67b5"))
    )
  )
  (nets
    (net (code "1") (name "/C0") (class "Default")
      (node (ref "C6") (pin "2") (pinfunction "2_2") (pintype "passive"))
      (node (ref "D6") (pin "1") (pinfunction "A_1") (pintype "passive"))
      (node (ref "R13") (pin "2") (pinfunction "2_2") (pintype "passive"))
    )
    (net (code "2") (name "/C1") (class "Default")
      (node (ref "D5") (pin "1") (pinfunction "A_1") (pintype "passive"))
      (node (ref "D6") (pin "2") (pinfunction "K_2") (pintype "passive"))
      (node (ref "R19") (pin "2") (pinfunction "2_2") (pintype "passive"))
    )
    (net (code "3") (name "/C2") (class "Default")
      (node (ref "D4") (pin "1") (pinfunction "A_1") (pintype "passive"))
      (node (ref "D5") (pin "2") (pinfunction "K_2") (pintype "passive"))
      (node (ref "R18") (pin "2") (pinfunction "2_2") (pintype "passive"))
    )
    (net (code "4") (name "/C3") (class "Default")
      (node (ref "D3") (pin "1") (pinfunction "A_1") (pintype "passive"))
      (node (ref "D4") (pin "2") (pinfunction "K_2") (pintype "passive"))
      (node (ref "R17") (pin "2") (pinfunction "2_2") (pintype "passive"))
    )
    (net (code "5") (name "/C4") (class "Default")
      (node (ref "D2") (pin "1") (pinfunction "A_1") (pintype "passive"))
      (node (ref "D3") (pin "2") (pinfunction "K_2") (pintype "passive"))
      (node (ref "R16") (pin "2") (pinfunction "2_2") (pintype "passive"))
    )
    (net (code "6") (name "/C5") (class "Default")
      (node (ref "D1") (pin "1") (pinfunction "A_1") (pintype "passive"))
      (node (ref "D2") (pin "2") (pinfunction "K_2") (pintype "passive"))
      (node (ref "R15") (pin "2") (pinfunction "2_2") (pintype "passive"))
    )
    (net (code "7") (name "/C6") (class "Default")
      (node (ref "D1") (pin "2") (pinfunction "K_2") (pintype "passive"))
      (node (ref "D12") (pin "1") (pinfunction "A_1") (pintype "passive"))
      (node (ref "DS12") (pin "2") (pinfunction "K_2") (pintype "passive"))
      (node (ref "Q1") (pin "2") (pinfunction "SOURCE_2") (pintype "passive"))
      (node (ref "R14") (pin "1") (pinfunction "1_1") (pintype "passive"))
      (node (ref "R14") (pin "2") (pinfunction "2_2") (pintype "passive"))
      (node (ref "R37") (pin "1") (pinfunction "1_1") (pintype "passive"))
    )
    (net (code "8") (name "/C7") (class "Default")
      (node (ref "D11") (pin "1") (pinfunction "A_1") (pintype "passive"))
      (node (ref "D12") (pin "2") (pinfunction "K_2") (pintype "passive"))
      (node (ref "R43") (pin "2") (pinfunction "2_2") (pintype "passive"))
    )
    (net (code "9") (name "/C8") (class "Default")
      (node (ref "D10") (pin "1") (pinfunction "A_1") (pintype "passive"))
      (node (ref "D11") (pin "2") (pinfunction "K_2") (pintype "passive"))
      (node (ref "R42") (pin "2") (pinfunction "2_2") (pintype "passive"))
    )
    (net (code "10") (name "/C9") (class "Default")
      (node (ref "D10") (pin "2") (pinfunction "K_2") (pintype "passive"))
      (node (ref "D9") (pin "1") (pinfunction "A_1") (pintype "passive"))
      (node (ref "R41") (pin "2") (pinfunction "2_2") (pintype "passive"))
    )
    (net (code "11") (name "/C10") (class "Default")
      (node (ref "D8") (pin "1") (pinfunction "A_1") (pintype "passive"))
      (node (ref "D9") (pin "2") (pinfunction "K_2") (pintype "passive"))
      (node (ref "R40") (pin "2") (pinfunction "2_2") (pintype "passive"))
    )
    (net (code "12") (name "/C11") (class "Default")
      (node (ref "D7") (pin "1") (pinfunction "A_1") (pintype "passive"))
      (node (ref "D8") (pin "2") (pinfunction "K_2") (pintype "passive"))
      (node (ref "R39") (pin "2") (pinfunction "2_2") (pintype "passive"))
    )
    (net (code "13") (name "/C12") (class "Default")
      (node (ref "D14") (pin "1") (pinfunction "A_1") (pintype "passive"))
      (node (ref "D7") (pin "2") (pinfunction "K_2") (pintype "passive"))
      (node (ref "DS14") (pin "2") (pinfunction "K_2") (pintype "passive"))
      (node (ref "Q7") (pin "2") (pinfunction "SOURCE_2") (pintype "passive"))
      (node (ref "R38") (pin "1") (pinfunction "1_1") (pintype "passive"))
      (node (ref "R38") (pin "2") (pinfunction "2_2") (pintype "passive"))
      (node (ref "R53") (pin "1") (pinfunction "1_1") (pintype "passive"))
    )
    (net (code "14") (name "/C13") (class "Default")
      (node (ref "D13") (pin "1") (pinfunction "A_1") (pintype "passive"))
      (node (ref "D14") (pin "2") (pinfunction "K_2") (pintype "passive"))
      (node (ref "R55") (pin "2") (pinfunction "2_2") (pintype "passive"))
    )
    (net (code "15") (name "/C14") (class "Default")
      (node (ref "D13") (pin "2") (pinfunction "K_2") (pintype "passive"))
      (node (ref "R54") (pin "2") (pinfunction "2_2") (pintype "passive"))
    )
    (net (code "16") (name "/CELL1") (class "Default")
      (node (ref "DS5") (pin "2") (pinfunction "K_2") (pintype "passive"))
      (node (ref "Q6") (pin "2") (pinfunction "SOURCE_2") (pintype "passive"))
      (node (ref "R11") (pin "1") (pinfunction "1_1") (pintype "passive"))
      (node (ref "R19") (pin "1") (pinfunction "1_1") (pintype "passive"))
    )
    (net (code "17") (name "/CELL2") (class "Default")
      (node (ref "DS4") (pin "2") (pinfunction "K_2") (pintype "passive"))
      (node (ref "Q5") (pin "2") (pinfunction "SOURCE_2") (pintype "passive"))
      (node (ref "R10") (pin "1") (pinfunction "1_1") (pintype "passive"))
      (node (ref "R18") (pin "1") (pinfunction "1_1") (pintype "passive"))
    )
    (net (code "18") (name "/CELL3") (class "Default")
      (node (ref "DS3") (pin "2") (pinfunction "K_2") (pintype "passive"))
      (node (ref "Q4") (pin "2") (pinfunction "SOURCE_2") (pintype "passive"))
      (node (ref "R17") (pin "1") (pinfunction "1_1") (pintype "passive"))
      (node (ref "R9") (pin "1") (pinfunction "1_1") (pintype "passive"))
    )
    (net (code "19") (name "/CELL4") (class "Default")
      (node (ref "DS2") (pin "2") (pinfunction "K_2") (pintype "passive"))
      (node (ref "Q3") (pin "2") (pinfunction "SOURCE_2") (pintype "passive"))
      (node (ref "R16") (pin "1") (pinfunction "1_1") (pintype "passive"))
      (node (ref "R8") (pin "1") (pinfunction "1_1") (pintype "passive"))
    )
    (net (code "20") (name "/CELL5") (class "Default")
      (node (ref "DS1") (pin "2") (pinfunction "K_2") (pintype "passive"))
      (node (ref "Q2") (pin "2") (pinfunction "SOURCE_2") (pintype "passive"))
      (node (ref "R15") (pin "1") (pinfunction "1_1") (pintype "passive"))
      (node (ref "R7") (pin "1") (pinfunction "1_1") (pintype "passive"))
    )
    (net (code "21") (name "/CELL7") (class "Default")
      (node (ref "DS11") (pin "2") (pinfunction "K_2") (pintype "passive"))
      (node (ref "Q12") (pin "2") (pinfunction "SOURCE_2") (pintype "passive"))
      (node (ref "R36") (pin "1") (pinfunction "1_1") (pintype "passive"))
      (node (ref "R43") (pin "1") (pinfunction "1_1") (pintype "passive"))
    )
    (net (code "22") (name "/CELL8") (class "Default")
      (node (ref "DS10") (pin "2") (pinfunction "K_2") (pintype "passive"))
      (node (ref "Q11") (pin "2") (pinfunction "SOURCE_2") (pintype "passive"))
      (node (ref "R35") (pin "1") (pinfunction "1_1") (pintype "passive"))
      (node (ref "R42") (pin "1") (pinfunction "1_1") (pintype "passive"))
    )
    (net (code "23") (name "/CELL9") (class "Default")
      (node (ref "DS9") (pin "2") (pinfunction "K_2") (pintype "passive"))
      (node (ref "Q10") (pin "2") (pinfunction "SOURCE_2") (pintype "passive"))
      (node (ref "R34") (pin "1") (pinfunction "1_1") (pintype "passive"))
      (node (ref "R41") (pin "1") (pinfunction "1_1") (pintype "passive"))
    )
    (net (code "24") (name "/CELL10") (class "Default")
      (node (ref "DS8") (pin "2") (pinfunction "K_2") (pintype "passive"))
      (node (ref "Q9") (pin "2") (pinfunction "SOURCE_2") (pintype "passive"))
      (node (ref "R33") (pin "1") (pinfunction "1_1") (pintype "passive"))
      (node (ref "R40") (pin "1") (pinfunction "1_1") (pintype "passive"))
    )
    (net (code "25") (name "/CELL11") (class "Default")
      (node (ref "DS7") (pin "2") (pinfunction "K_2") (pintype "passive"))
      (node (ref "Q8") (pin "2") (pinfunction "SOURCE_2") (pintype "passive"))
      (node (ref "R32") (pin "1") (pinfunction "1_1") (pintype "passive"))
      (node (ref "R39") (pin "1") (pinfunction "1_1") (pintype "passive"))
    )
    (net (code "26") (name "/CELL13") (class "Default")
      (node (ref "DS13") (pin "2") (pinfunction "K_2") (pintype "passive"))
      (node (ref "Q14") (pin "2") (pinfunction "SOURCE_2") (pintype "passive"))
      (node (ref "R52") (pin "1") (pinfunction "1_1") (pintype "passive"))
      (node (ref "R55") (pin "1") (pinfunction "1_1") (pintype "passive"))
    )
    (net (code "27") (name "/CELL14") (class "Default")
      (node (ref "Q13") (pin "2") (pinfunction "SOURCE_2") (pintype "passive"))
      (node (ref "R54") (pin "1") (pinfunction "1_1") (pintype "passive"))
    )
    (net (code "28") (name "/S1") (class "Default")
      (node (ref "C7") (pin "2") (pinfunction "2_2") (pintype "passive"))
      (node (ref "R25") (pin "2") (pinfunction "2_2") (pintype "passive"))
    )
    (net (code "29") (name "/S2") (class "Default")
      (node (ref "C12") (pin "2") (pinfunction "2_2") (pintype "passive"))
      (node (ref "R24") (pin "2") (pinfunction "2_2") (pintype "passive"))
    )
    (net (code "30") (name "/S3") (class "Default")
      (node (ref "C11") (pin "2") (pinfunction "2_2") (pintype "passive"))
      (node (ref "R23") (pin "2") (pinfunction "2_2") (pintype "passive"))
    )
    (net (code "31") (name "/S4") (class "Default")
      (node (ref "C10") (pin "2") (pinfunction "2_2") (pintype "passive"))
      (node (ref "R22") (pin "2") (pinfunction "2_2") (pintype "passive"))
    )
    (net (code "32") (name "/S5") (class "Default")
      (node (ref "C9") (pin "2") (pinfunction "2_2") (pintype "passive"))
      (node (ref "R21") (pin "2") (pinfunction "2_2") (pintype "passive"))
    )
    (net (code "33") (name "/S6") (class "Default")
      (node (ref "C8") (pin "2") (pinfunction "2_2") (pintype "passive"))
      (node (ref "R20") (pin "2") (pinfunction "2_2") (pintype "passive"))
    )
    (net (code "34") (name "/S7") (class "Default")
      (node (ref "C18") (pin "2") (pinfunction "2_2") (pintype "passive"))
      (node (ref "R49") (pin "2") (pinfunction "2_2") (pintype "passive"))
    )
    (net (code "35") (name "/S8") (class "Default")
      (node (ref "C17") (pin "2") (pinfunction "2_2") (pintype "passive"))
      (node (ref "R48") (pin "2") (pinfunction "2_2") (pintype "passive"))
    )
    (net (code "36") (name "/S9") (class "Default")
      (node (ref "C16") (pin "2") (pinfunction "2_2") (pintype "passive"))
      (node (ref "R47") (pin "2") (pinfunction "2_2") (pintype "passive"))
    )
    (net (code "37") (name "/S10") (class "Default")
      (node (ref "C15") (pin "2") (pinfunction "2_2") (pintype "passive"))
      (node (ref "R46") (pin "2") (pinfunction "2_2") (pintype "passive"))
    )
    (net (code "38") (name "/S11") (class "Default")
      (node (ref "C14") (pin "2") (pinfunction "2_2") (pintype "passive"))
      (node (ref "R45") (pin "2") (pinfunction "2_2") (pintype "passive"))
    )
    (net (code "39") (name "/S12") (class "Default")
      (node (ref "C13") (pin "2") (pinfunction "2_2") (pintype "passive"))
      (node (ref "R44") (pin "2") (pinfunction "2_2") (pintype "passive"))
    )
    (net (code "40") (name "/S13") (class "Default")
      (node (ref "C20") (pin "2") (pinfunction "2_2") (pintype "passive"))
      (node (ref "R57") (pin "2") (pinfunction "2_2") (pintype "passive"))
    )
    (net (code "41") (name "/S14") (class "Default")
      (node (ref "C19") (pin "2") (pinfunction "2_2") (pintype "passive"))
      (node (ref "R56") (pin "2") (pinfunction "2_2") (pintype "passive"))
    )
    (net (code "42") (name "GND") (class "Default")
      (node (ref "C10") (pin "1") (pinfunction "1_1") (pintype "passive"))
      (node (ref "C11") (pin "1") (pinfunction "1_1") (pintype "passive"))
      (node (ref "C12") (pin "1") (pinfunction "1_1") (pintype "passive"))
      (node (ref "C13") (pin "1") (pinfunction "1_1") (pintype "passive"))
      (node (ref "C14") (pin "1") (pinfunction "1_1") (pintype "passive"))
      (node (ref "C15") (pin "1") (pinfunction "1_1") (pintype "passive"))
      (node (ref "C16") (pin "1") (pinfunction "1_1") (pintype "passive"))
      (node (ref "C17") (pin "1") (pinfunction "1_1") (pintype "passive"))
      (node (ref "C18") (pin "1") (pinfunction "1_1") (pintype "passive"))
      (node (ref "C19") (pin "1") (pinfunction "1_1") (pintype "passive"))
      (node (ref "C20") (pin "1") (pinfunction "1_1") (pintype "passive"))
      (node (ref "C6") (pin "1") (pinfunction "1_1") (pintype "passive"))
      (node (ref "C7") (pin "1") (pinfunction "1_1") (pintype "passive"))
      (node (ref "C8") (pin "1") (pinfunction "1_1") (pintype "passive"))
      (node (ref "C9") (pin "1") (pinfunction "1_1") (pintype "passive"))
    )
    (net (code "43") (name "Net-(DS1-A)") (class "Default")
      (node (ref "DS1") (pin "1") (pinfunction "A_1") (pintype "passive"))
      (node (ref "R1") (pin "1") (pinfunction "1_1") (pintype "passive"))
    )
    (net (code "44") (name "Net-(DS2-A)") (class "Default")
      (node (ref "DS2") (pin "1") (pinfunction "A_1") (pintype "passive"))
      (node (ref "R2") (pin "1") (pinfunction "1_1") (pintype "passive"))
    )
    (net (code "45") (name "Net-(DS3-A)") (class "Default")
      (node (ref "DS3") (pin "1") (pinfunction "A_1") (pintype "passive"))
      (node (ref "R3") (pin "1") (pinfunction "1_1") (pintype "passive"))
    )
    (net (code "46") (name "Net-(DS4-A)") (class "Default")
      (node (ref "DS4") (pin "1") (pinfunction "A_1") (pintype "passive"))
      (node (ref "R4") (pin "1") (pinfunction "1_1") (pintype "passive"))
    )
    (net (code "47") (name "Net-(DS5-A)") (class "Default")
      (node (ref "DS5") (pin "1") (pinfunction "A_1") (pintype "passive"))
      (node (ref "R5") (pin "1") (pinfunction "1_1") (pintype "passive"))
    )
    (net (code "48") (name "Net-(DS6-A)") (class "Default")
      (node (ref "DS6") (pin "1") (pinfunction "A_1") (pintype "passive"))
      (node (ref "R6") (pin "1") (pinfunction "1_1") (pintype "passive"))
    )
    (net (code "49") (name "Net-(DS6-K)") (class "Default")
      (node (ref "DS6") (pin "2") (pinfunction "K_2") (pintype "passive"))
      (node (ref "R12") (pin "1") (pinfunction "1_1") (pintype "passive"))
      (node (ref "R13") (pin "1") (pinfunction "1_1") (pintype "passive"))
    )
    (net (code "50") (name "Net-(DS7-A)") (class "Default")
      (node (ref "DS7") (pin "1") (pinfunction "A_1") (pintype "passive"))
      (node (ref "R26") (pin "1") (pinfunction "1_1") (pintype "passive"))
    )
    (net (code "51") (name "Net-(DS8-A)") (class "Default")
      (node (ref "DS8") (pin "1") (pinfunction "A_1") (pintype "passive"))
      (node (ref "R27") (pin "1") (pinfunction "1_1") (pintype "passive"))
    )
    (net (code "52") (name "Net-(DS9-A)") (class "Default")
      (node (ref "DS9") (pin "1") (pinfunction "A_1") (pintype "passive"))
      (node (ref "R28") (pin "1") (pinfunction "1_1") (pintype "passive"))
    )
    (net (code "53") (name "Net-(DS10-A)") (class "Default")
      (node (ref "DS10") (pin "1") (pinfunction "A_1") (pintype "passive"))
      (node (ref "R29") (pin "1") (pinfunction "1_1") (pintype "passive"))
    )
    (net (code "54") (name "Net-(DS11-A)") (class "Default")
      (node (ref "DS11") (pin "1") (pinfunction "A_1") (pintype "passive"))
      (node (ref "R30") (pin "1") (pinfunction "1_1") (pintype "passive"))
    )
    (net (code "55") (name "Net-(DS12-A)") (class "Default")
      (node (ref "DS12") (pin "1") (pinfunction "A_1") (pintype "passive"))
      (node (ref "R31") (pin "1") (pinfunction "1_1") (pintype "passive"))
    )
    (net (code "56") (name "Net-(DS13-A)") (class "Default")
      (node (ref "DS13") (pin "1") (pinfunction "A_1") (pintype "passive"))
      (node (ref "R50") (pin "1") (pinfunction "1_1") (pintype "passive"))
    )
    (net (code "57") (name "Net-(DS14-A)") (class "Default")
      (node (ref "DS14") (pin "1") (pinfunction "A_1") (pintype "passive"))
      (node (ref "R51") (pin "1") (pinfunction "1_1") (pintype "passive"))
    )
    (net (code "58") (name "Net-(Q1-DRAIN)") (class "Default")
      (node (ref "Q1") (pin "3") (pinfunction "DRAIN_3") (pintype "passive"))
      (node (ref "R1") (pin "2") (pinfunction "2_2") (pintype "passive"))
      (node (ref "R7") (pin "2") (pinfunction "2_2") (pintype "passive"))
    )
    (net (code "59") (name "Net-(Q1-GATE)") (class "Default")
      (node (ref "Q1") (pin "1") (pinfunction "GATE_1") (pintype "passive"))
      (node (ref "R20") (pin "1") (pinfunction "1_1") (pintype "passive"))
    )
    (net (code "60") (name "Net-(Q2-DRAIN)") (class "Default")
      (node (ref "Q2") (pin "3") (pinfunction "DRAIN_3") (pintype "passive"))
      (node (ref "R2") (pin "2") (pinfunction "2_2") (pintype "passive"))
      (node (ref "R8") (pin "2") (pinfunction "2_2") (pintype "passive"))
    )
    (net (code "61") (name "Net-(Q2-GATE)") (class "Default")
      (node (ref "Q2") (pin "1") (pinfunction "GATE_1") (pintype "passive"))
      (node (ref "R21") (pin "1") (pinfunction "1_1") (pintype "passive"))
    )
    (net (code "62") (name "Net-(Q3-DRAIN)") (class "Default")
      (node (ref "Q3") (pin "3") (pinfunction "DRAIN_3") (pintype "passive"))
      (node (ref "R3") (pin "2") (pinfunction "2_2") (pintype "passive"))
      (node (ref "R9") (pin "2") (pinfunction "2_2") (pintype "passive"))
    )
    (net (code "63") (name "Net-(Q3-GATE)") (class "Default")
      (node (ref "Q3") (pin "1") (pinfunction "GATE_1") (pintype "passive"))
      (node (ref "R22") (pin "1") (pinfunction "1_1") (pintype "passive"))
    )
    (net (code "64") (name "Net-(Q4-DRAIN)") (class "Default")
      (node (ref "Q4") (pin "3") (pinfunction "DRAIN_3") (pintype "passive"))
      (node (ref "R10") (pin "2") (pinfunction "2_2") (pintype "passive"))
      (node (ref "R4") (pin "2") (pinfunction "2_2") (pintype "passive"))
    )
    (net (code "65") (name "Net-(Q4-GATE)") (class "Default")
      (node (ref "Q4") (pin "1") (pinfunction "GATE_1") (pintype "passive"))
      (node (ref "R23") (pin "1") (pinfunction "1_1") (pintype "passive"))
    )
    (net (code "66") (name "Net-(Q5-DRAIN)") (class "Default")
      (node (ref "Q5") (pin "3") (pinfunction "DRAIN_3") (pintype "passive"))
      (node (ref "R11") (pin "2") (pinfunction "2_2") (pintype "passive"))
      (node (ref "R5") (pin "2") (pinfunction "2_2") (pintype "passive"))
    )
    (net (code "67") (name "Net-(Q5-GATE)") (class "Default")
      (node (ref "Q5") (pin "1") (pinfunction "GATE_1") (pintype "passive"))
      (node (ref "R24") (pin "1") (pinfunction "1_1") (pintype "passive"))
    )
    (net (code "68") (name "Net-(Q6-DRAIN)") (class "Default")
      (node (ref "Q6") (pin "3") (pinfunction "DRAIN_3") (pintype "passive"))
      (node (ref "R12") (pin "2") (pinfunction "2_2") (pintype "passive"))
      (node (ref "R6") (pin "2") (pinfunction "2_2") (pintype "passive"))
    )
    (net (code "69") (name "Net-(Q6-GATE)") (class "Default")
      (node (ref "Q6") (pin "1") (pinfunction "GATE_1") (pintype "passive"))
      (node (ref "R25") (pin "1") (pinfunction "1_1") (pintype "passive"))
    )
    (net (code "70") (name "Net-(Q7-DRAIN)") (class "Default")
      (node (ref "Q7") (pin "3") (pinfunction "DRAIN_3") (pintype "passive"))
      (node (ref "R26") (pin "2") (pinfunction "2_2") (pintype "passive"))
      (node (ref "R32") (pin "2") (pinfunction "2_2") (pintype "passive"))
    )
    (net (code "71") (name "Net-(Q7-GATE)") (class "Default")
      (node (ref "Q7") (pin "1") (pinfunction "GATE_1") (pintype "passive"))
      (node (ref "R44") (pin "1") (pinfunction "1_1") (pintype "passive"))
    )
    (net (code "72") (name "Net-(Q8-DRAIN)") (class "Default")
      (node (ref "Q8") (pin "3") (pinfunction "DRAIN_3") (pintype "passive"))
      (node (ref "R27") (pin "2") (pinfunction "2_2") (pintype "passive"))
      (node (ref "R33") (pin "2") (pinfunction "2_2") (pintype "passive"))
    )
    (net (code "73") (name "Net-(Q8-GATE)") (class "Default")
      (node (ref "Q8") (pin "1") (pinfunction "GATE_1") (pintype "passive"))
      (node (ref "R45") (pin "1") (pinfunction "1_1") (pintype "passive"))
    )
    (net (code "74") (name "Net-(Q9-DRAIN)") (class "Default")
      (node (ref "Q9") (pin "3") (pinfunction "DRAIN_3") (pintype "passive"))
      (node (ref "R28") (pin "2") (pinfunction "2_2") (pintype "passive"))
      (node (ref "R34") (pin "2") (pinfunction "2_2") (pintype "passive"))
    )
    (net (code "75") (name "Net-(Q9-GATE)") (class "Default")
      (node (ref "Q9") (pin "1") (pinfunction "GATE_1") (pintype "passive"))
      (node (ref "R46") (pin "1") (pinfunction "1_1") (pintype "passive"))
    )
    (net (code "76") (name "Net-(Q10-DRAIN)") (class "Default")
      (node (ref "Q10") (pin "3") (pinfunction "DRAIN_3") (pintype "passive"))
      (node (ref "R29") (pin "2") (pinfunction "2_2") (pintype "passive"))
      (node (ref "R35") (pin "2") (pinfunction "2_2") (pintype "passive"))
    )
    (net (code "77") (name "Net-(Q10-GATE)") (class "Default")
      (node (ref "Q10") (pin "1") (pinfunction "GATE_1") (pintype "passive"))
      (node (ref "R47") (pin "1") (pinfunction "1_1") (pintype "passive"))
    )
    (net (code "78") (name "Net-(Q11-DRAIN)") (class "Default")
      (node (ref "Q11") (pin "3") (pinfunction "DRAIN_3") (pintype "passive"))
      (node (ref "R30") (pin "2") (pinfunction "2_2") (pintype "passive"))
      (node (ref "R36") (pin "2") (pinfunction "2_2") (pintype "passive"))
    )
    (net (code "79") (name "Net-(Q11-GATE)") (class "Default")
      (node (ref "Q11") (pin "1") (pinfunction "GATE_1") (pintype "passive"))
      (node (ref "R48") (pin "1") (pinfunction "1_1") (pintype "passive"))
    )
    (net (code "80") (name "Net-(Q12-DRAIN)") (class "Default")
      (node (ref "Q12") (pin "3") (pinfunction "DRAIN_3") (pintype "passive"))
      (node (ref "R31") (pin "2") (pinfunction "2_2") (pintype "passive"))
      (node (ref "R37") (pin "2") (pinfunction "2_2") (pintype "passive"))
    )
    (net (code "81") (name "Net-(Q12-GATE)") (class "Default")
      (node (ref "Q12") (pin "1") (pinfunction "GATE_1") (pintype "passive"))
      (node (ref "R49") (pin "1") (pinfunction "1_1") (pintype "passive"))
    )
    (net (code "82") (name "Net-(Q13-DRAIN)") (class "Default")
      (node (ref "Q13") (pin "3") (pinfunction "DRAIN_3") (pintype "passive"))
      (node (ref "R50") (pin "2") (pinfunction "2_2") (pintype "passive"))
      (node (ref "R52") (pin "2") (pinfunction "2_2") (pintype "passive"))
    )
    (net (code "83") (name "Net-(Q13-GATE)") (class "Default")
      (node (ref "Q13") (pin "1") (pinfunction "GATE_1") (pintype "passive"))
      (node (ref "R56") (pin "1") (pinfunction "1_1") (pintype "passive"))
    )
    (net (code "84") (name "Net-(Q14-DRAIN)") (class "Default")
      (node (ref "Q14") (pin "3") (pinfunction "DRAIN_3") (pintype "passive"))
      (node (ref "R51") (pin "2") (pinfunction "2_2") (pintype "passive"))
      (node (ref "R53") (pin "2") (pinfunction "2_2") (pintype "passive"))
    )
    (net (code "85") (name "Net-(Q14-GATE)") (class "Default")
      (node (ref "Q14") (pin "1") (pinfunction "GATE_1") (pintype "passive"))
      (node (ref "R57") (pin "1") (pinfunction "1_1") (pintype "passive"))
    )
  )
)
